# IPMI.net
KiCad netlist of a schematic drawn in Altium Designer
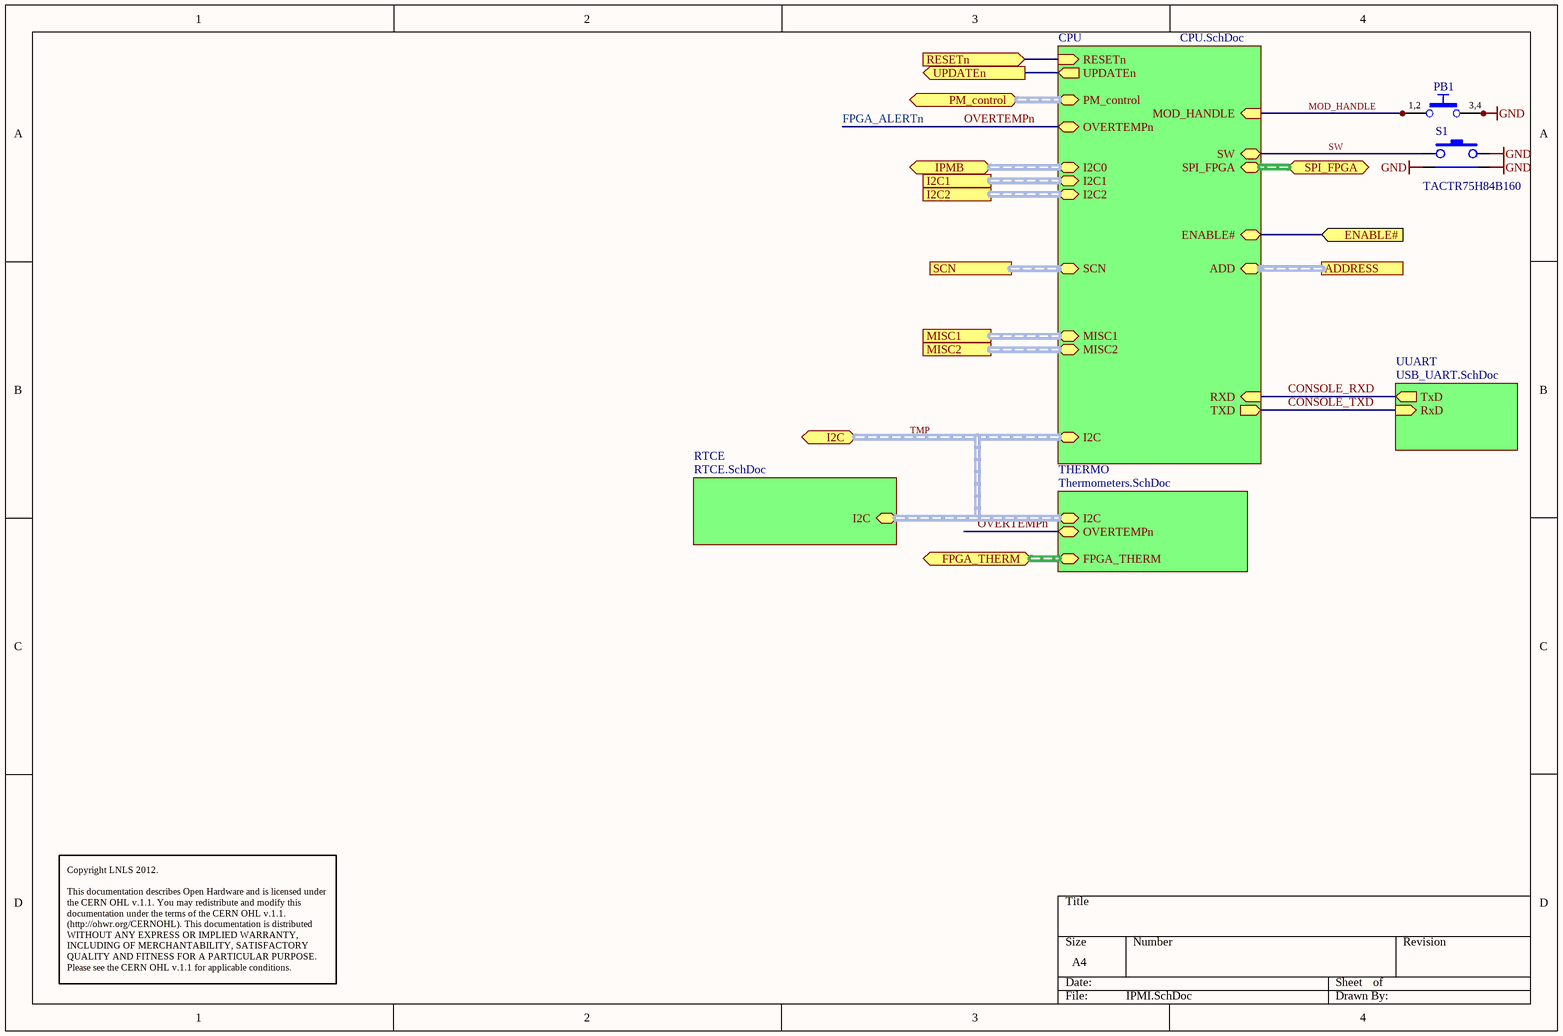
[diagram p0: IPMI.SchDoc]

(export (version "E")
  (design (tool "Eeschema 10.0.6"))
  (components
    (comp (ref "PB1")
      (value "Push Button")
      (footprint "SW_C&K_HDT0001")
      (description "Push-Button Switch SPDT")
      (fields
        (field (name "PART NUMBER") "SW_C&K_HDT0001")
        (field (name "MANUFACTURER") "C&K")
        (field (name "AUTHOR") "CERN DEM JLC")
      )
      (libsource (lib "Eletro-mechanical") (part "PB SPST 12NO-34NO"))
    )
    (comp (ref "S1")
      (value "TACTR75H84B160")
      (footprint "PB_ALPS_SKHHLQA010")
      (description "Push button")
      (libsource (lib "LIBRARY_SCH") (part "SW-PB_RA_5.8mm"))
    )
  )
  (nets
    (net (code "23") (name "/MOD_HANDLE") (class "Default")
      (node (ref "PB1") (pin "1") (pinfunction "1_1") (pintype "passive"))
      (node (ref "PB1") (pin "2") (pinfunction "2_2") (pintype "passive"))
    )
    (net (code "28") (name "/SW") (class "Default")
      (node (ref "S1") (pin "1") (pinfunction "1_1") (pintype "passive"))
    )
    (net (code "31") (name "GND") (class "Default")
      (node (ref "PB1") (pin "3") (pinfunction "3_3") (pintype "passive"))
      (node (ref "PB1") (pin "4") (pinfunction "4_4") (pintype "passive"))
      (node (ref "S1") (pin "2") (pinfunction "2_2") (pintype "passive"))
      (node (ref "S1") (pin "3") (pinfunction "3_3") (pintype "passive"))
      (node (ref "S1") (pin "4") (pinfunction "4_4") (pintype "passive"))
    )
  )
)
